# round_board.net
KiCad netlist of a schematic drawn in EAGLE
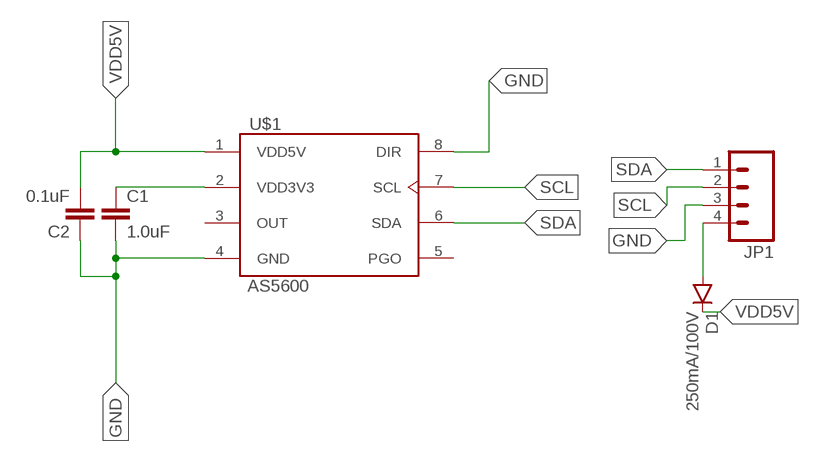
[diagram p0: schematic, sheet 1]

(export (version "E")
  (design (tool "Eeschema 10.0.6"))
  (components
    (comp (ref "C1")
      (value "1.0uF")
      (footprint "eagle-import:0603-CAP")
      (libsource (lib "eagle-import") (part "1.0UF-16V-10%(0603)"))
    )
    (comp (ref "C2")
      (value "0.1uF")
      (footprint "eagle-import:0603-CAP")
      (libsource (lib "eagle-import") (part "0.1UF-25V(+80/-20%)(0603)"))
    )
    (comp (ref "D1")
      (value "250mA/100V")
      (footprint "eagle-import:SOD-323")
      (libsource (lib "eagle-import") (part "DIODEBAS16"))
    )
    (comp (ref "JP1")
      (value "M04LOCK")
      (footprint "eagle-import:1X04_LOCK")
      (libsource (lib "eagle-import") (part "M04LOCK"))
    )
    (comp (ref "U$1")
      (value "AS5600")
      (footprint "eagle-import:SOIC8")
      (libsource (lib "eagle-import") (part "AS5600"))
    )
  )
  (nets
    (net (code "1") (name "GND") (class "Default")
      (node (ref "C1") (pin "2") (pinfunction "2_2") (pintype "passive"))
      (node (ref "C2") (pin "1") (pinfunction "1_1") (pintype "passive"))
      (node (ref "JP1") (pin "3") (pinfunction "3_3") (pintype "passive"))
      (node (ref "U$1") (pin "4") (pinfunction "GND_4") (pintype "power_in"))
      (node (ref "U$1") (pin "8") (pinfunction "DIR_8") (pintype "bidirectional"))
    )
    (net (code "2") (name "Net-(D1-PadA)") (class "Default")
      (node (ref "D1") (pin "A") (pinfunction "A_A") (pintype "passive"))
      (node (ref "JP1") (pin "4") (pinfunction "4_4") (pintype "passive"))
    )
    (net (code "3") (name "Net-(U$1-VDD3V3)") (class "Default")
      (node (ref "C1") (pin "1") (pinfunction "1_1") (pintype "passive"))
      (node (ref "U$1") (pin "2") (pinfunction "VDD3V3_2") (pintype "power_in"))
    )
    (net (code "4") (name "SCL") (class "Default")
      (node (ref "JP1") (pin "2") (pinfunction "2_2") (pintype "passive"))
      (node (ref "U$1") (pin "7") (pinfunction "SCL_7") (pintype "input"))
    )
    (net (code "5") (name "SDA") (class "Default")
      (node (ref "JP1") (pin "1") (pinfunction "1_1") (pintype "passive"))
      (node (ref "U$1") (pin "6") (pinfunction "SDA_6") (pintype "bidirectional"))
    )
    (net (code "6") (name "VDD5V") (class "Default")
      (node (ref "C2") (pin "2") (pinfunction "2_2") (pintype "passive"))
      (node (ref "D1") (pin "C") (pinfunction "C_C") (pintype "passive"))
      (node (ref "U$1") (pin "1") (pinfunction "VDD5V_1") (pintype "power_in"))
    )
    (net (code "7") (name "unconnected-(U$1-OUT-Pad3)") (class "Default")
      (node (ref "U$1") (pin "3") (pinfunction "OUT_3") (pintype "output"))
    )
    (net (code "8") (name "unconnected-(U$1-PGO-Pad5)") (class "Default")
      (node (ref "U$1") (pin "5") (pinfunction "PGO_5") (pintype "bidirectional"))
    )
  )
)
